# Seeed_Studio_XIAO_nRF52840_v1_1.net
KiCad netlist of a schematic drawn in EAGLE
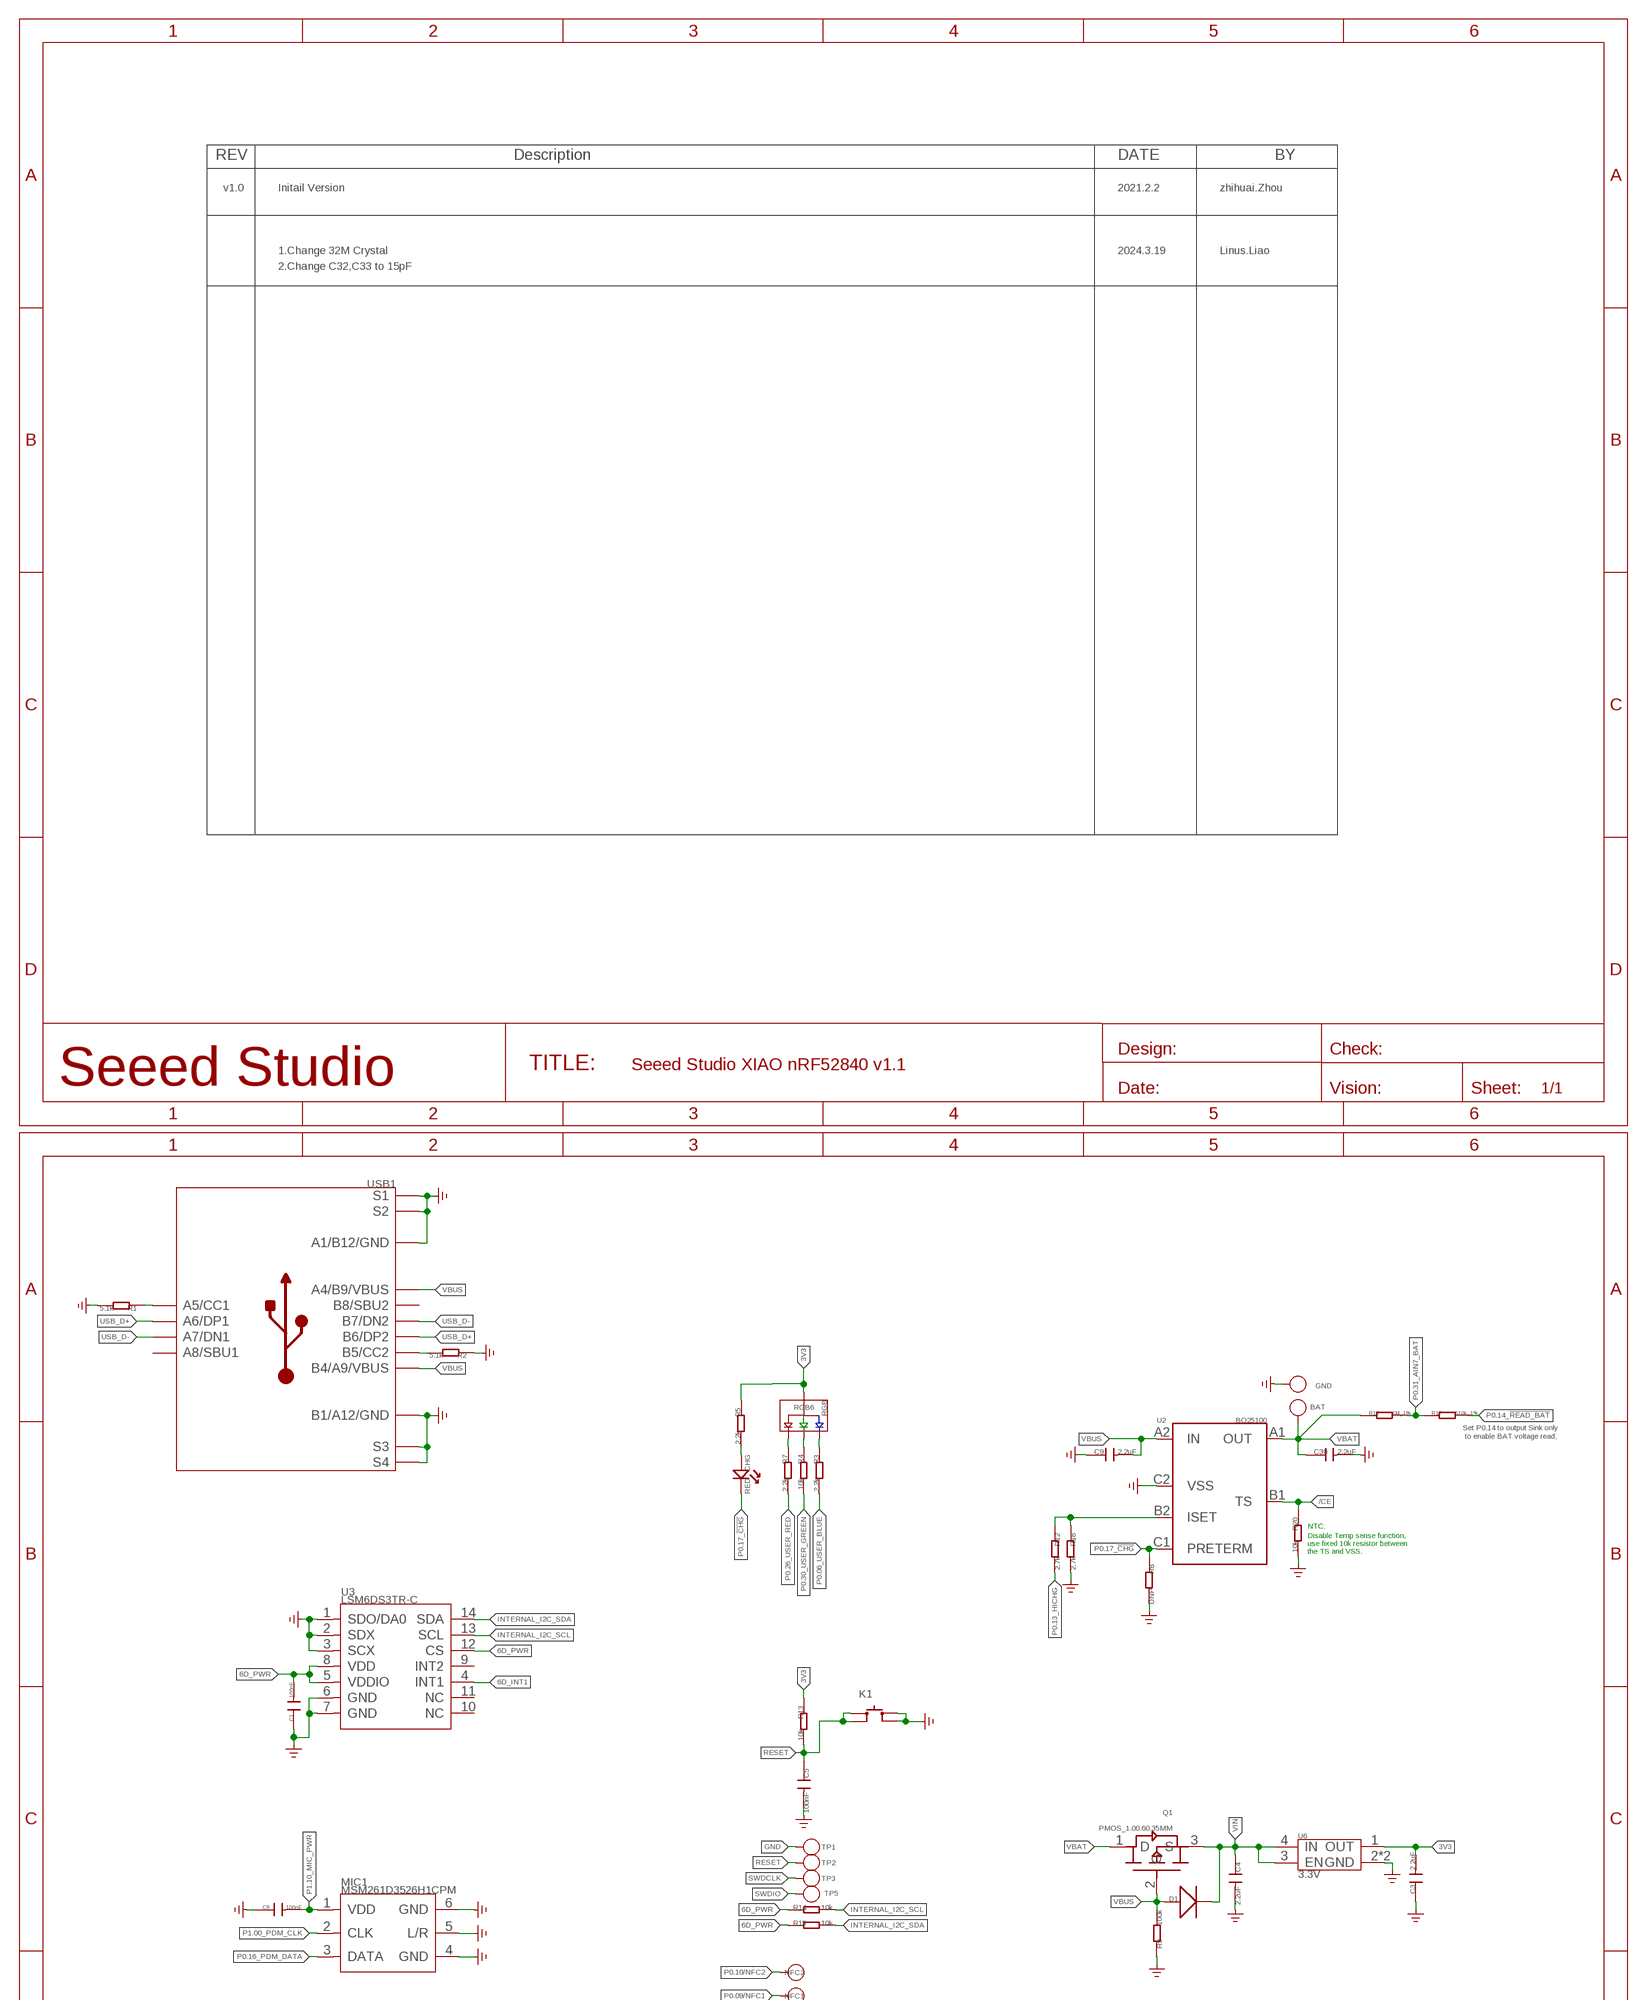
[diagram p0: schematic, sheet 1, part 1 of 2]
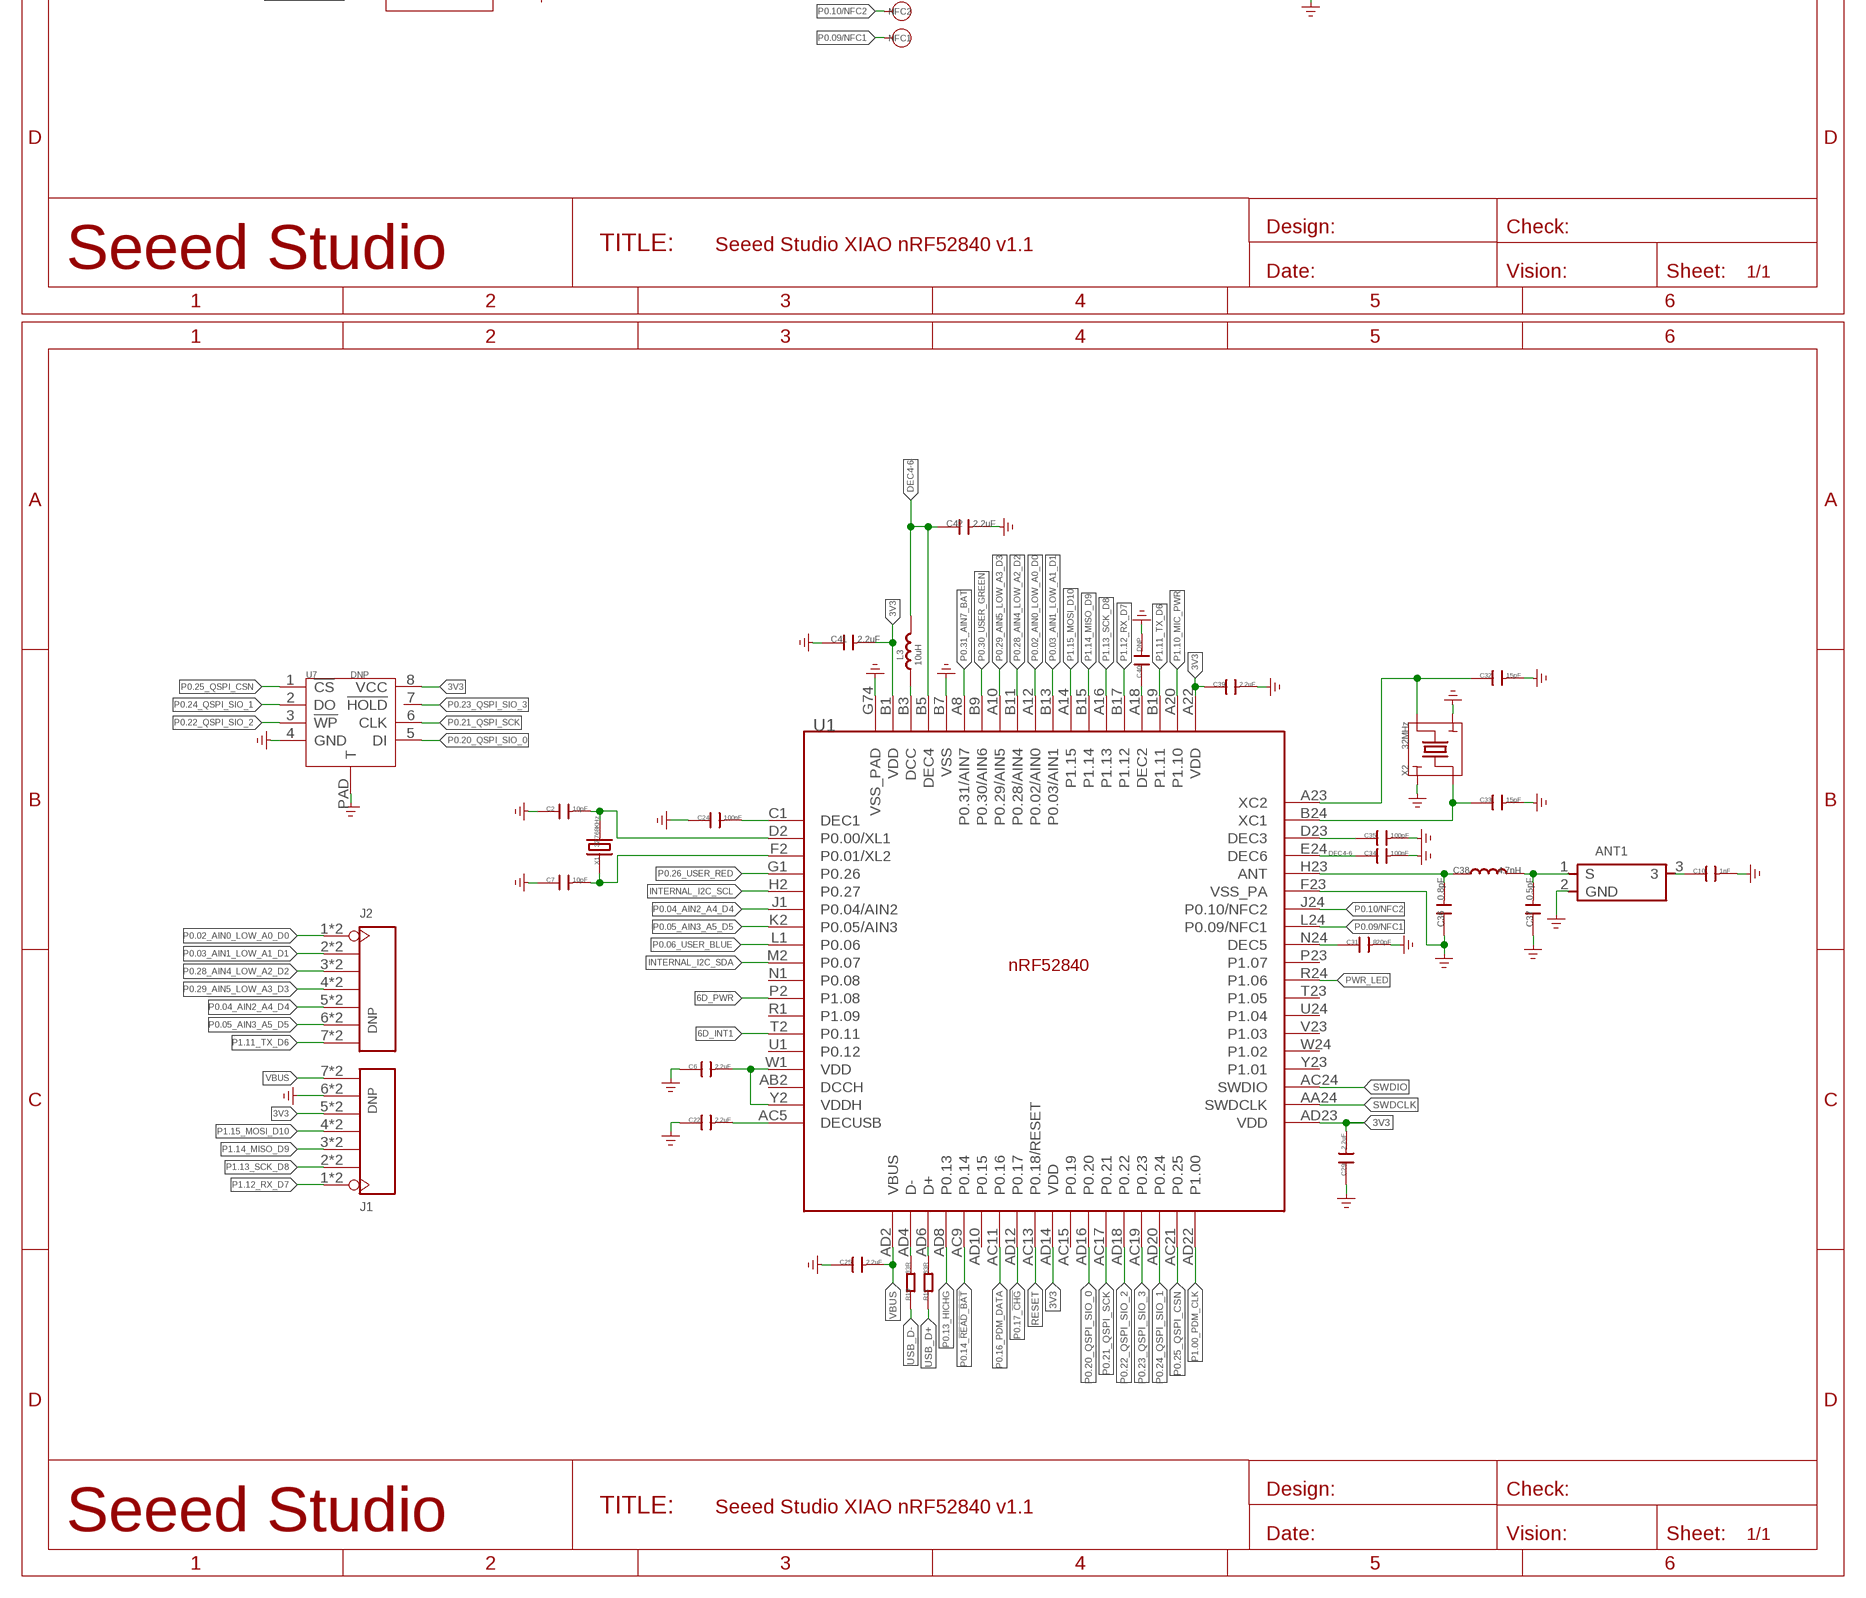
[diagram p1: schematic, sheet 1, part 2 of 2]

(export (version "E")
  (design (tool "Eeschema 10.0.6"))
  (components
    (comp (ref "ANT1")
      (value "ANTENNA-AN3216")
      (footprint "eagle-import:ANT-SMD3P-3.2X1.6X1.04MM")
      (libsource (lib "eagle-import") (part "ANTENNA-AN3216"))
    )
    (comp (ref "BAT")
      (value "TEST-POINT'4080'")
      (footprint "eagle-import:TP-80X40MIL")
      (libsource (lib "eagle-import") (part "TEST-POINT'4080'"))
    )
    (comp (ref "C1")
      (value "100nF")
      (footprint "eagle-import:C0201")
      (libsource (lib "eagle-import") (part "C-0201"))
    )
    (comp (ref "C2")
      (value "10pF")
      (footprint "eagle-import:C0201")
      (libsource (lib "eagle-import") (part "C-0201"))
    )
    (comp (ref "C3")
      (value "2.2uF")
      (footprint "eagle-import:C0201")
      (libsource (lib "eagle-import") (part "C-0201"))
    )
    (comp (ref "C4")
      (value "2.2uF")
      (footprint "eagle-import:C0201")
      (libsource (lib "eagle-import") (part "C-0201"))
    )
    (comp (ref "C5")
      (value "100nF")
      (footprint "eagle-import:C0201")
      (libsource (lib "eagle-import") (part "C-0201"))
    )
    (comp (ref "C6")
      (value "2.2uF")
      (footprint "eagle-import:C0201")
      (libsource (lib "eagle-import") (part "C-0201"))
    )
    (comp (ref "C7")
      (value "10pF")
      (footprint "eagle-import:C0201")
      (libsource (lib "eagle-import") (part "C-0201"))
    )
    (comp (ref "C8")
      (value "100nF")
      (footprint "eagle-import:C0201")
      (libsource (lib "eagle-import") (part "C-0201"))
    )
    (comp (ref "C9")
      (value "2.2uF")
      (footprint "eagle-import:C0201")
      (libsource (lib "eagle-import") (part "C-0201"))
    )
    (comp (ref "C10")
      (value "1nF")
      (footprint "eagle-import:C0402")
      (libsource (lib "eagle-import") (part "C-0402"))
    )
    (comp (ref "C22")
      (value "2.2uF")
      (footprint "eagle-import:C0201")
      (libsource (lib "eagle-import") (part "C-0201"))
    )
    (comp (ref "C24")
      (value "100nF")
      (footprint "eagle-import:C0201")
      (libsource (lib "eagle-import") (part "C-0201"))
    )
    (comp (ref "C25")
      (value "2.2uF")
      (footprint "eagle-import:C0201")
      (libsource (lib "eagle-import") (part "C-0201"))
    )
    (comp (ref "C29")
      (value "2.2uF")
      (footprint "eagle-import:C0201")
      (libsource (lib "eagle-import") (part "C-0201"))
    )
    (comp (ref "C30")
      (value "2.2uF")
      (footprint "eagle-import:C0201")
      (libsource (lib "eagle-import") (part "C-0201"))
    )
    (comp (ref "C31")
      (value "820pF")
      (footprint "eagle-import:C0201")
      (libsource (lib "eagle-import") (part "C-0201"))
    )
    (comp (ref "C32")
      (value "15pF")
      (footprint "eagle-import:C0201")
      (libsource (lib "eagle-import") (part "C-0201"))
    )
    (comp (ref "C33")
      (value "15pF")
      (footprint "eagle-import:C0201")
      (libsource (lib "eagle-import") (part "C-0201"))
    )
    (comp (ref "C34")
      (value "100nF")
      (footprint "eagle-import:C0201")
      (libsource (lib "eagle-import") (part "C-0201"))
    )
    (comp (ref "C35")
      (value "100pF")
      (footprint "eagle-import:C0201")
      (libsource (lib "eagle-import") (part "C-0201"))
    )
    (comp (ref "C36")
      (value "0.8pF")
      (footprint "eagle-import:C0201")
      (libsource (lib "eagle-import") (part "C-0201"))
    )
    (comp (ref "C37")
      (value "0.5pF")
      (footprint "eagle-import:C0201")
      (libsource (lib "eagle-import") (part "C-0201"))
    )
    (comp (ref "C38")
      (value "4.7nH")
      (footprint "eagle-import:L0201")
      (libsource (lib "eagle-import") (part "L0201"))
    )
    (comp (ref "C39")
      (value "2.2uF")
      (footprint "eagle-import:C0201")
      (libsource (lib "eagle-import") (part "C-0201"))
    )
    (comp (ref "C40")
      (value "DNP")
      (footprint "eagle-import:C0201")
      (libsource (lib "eagle-import") (part "C-0201"))
    )
    (comp (ref "C41")
      (value "2.2uF")
      (footprint "eagle-import:C0201")
      (libsource (lib "eagle-import") (part "C-0201"))
    )
    (comp (ref "C42")
      (value "2.2uF")
      (footprint "eagle-import:C0201")
      (libsource (lib "eagle-import") (part "C-0201"))
    )
    (comp (ref "CHG")
      (value "RED")
      (footprint "eagle-import:LED-0402")
      (libsource (lib "eagle-import") (part "LED-0402"))
    )
    (comp (ref "D1")
      (value "DIODE'0603'")
      (footprint "eagle-import:SOD-523")
      (libsource (lib "eagle-import") (part "DIODE'0603'"))
    )
    (comp (ref "GND")
      (value "GND")
      (footprint "eagle-import:TP-80X40MIL")
      (libsource (lib "eagle-import") (part "TEST-POINT'4080'"))
    )
    (comp (ref "J1")
      (value "DNP")
      (footprint "eagle-import:H7-HALF-HOLE-2.54")
      (libsource (lib "eagle-import") (part "HEADER-7P-HALF-HOLE-2.54"))
    )
    (comp (ref "J2")
      (value "DNP")
      (footprint "eagle-import:H7-HALF-HOLE-2.54")
      (libsource (lib "eagle-import") (part "HEADER-7P-HALF-HOLE-2.54"))
    )
    (comp (ref "K1")
      (value "BUTTON-4P")
      (footprint "eagle-import:SW4-SMD-2.8-2.6X1.6X0.53MM")
      (libsource (lib "eagle-import") (part "BUTTON-4P"))
    )
    (comp (ref "L3")
      (value "10uH")
      (footprint "eagle-import:L0603")
      (libsource (lib "eagle-import") (part "L0603"))
    )
    (comp (ref "MIC1")
      (value "MSM261D3526H1CPM")
      (footprint "eagle-import:MIC6P-3.5X2.65X0.94MM")
      (libsource (lib "eagle-import") (part "MIC-MSM261D3526H1CPM"))
    )
    (comp (ref "NFC1")
      (value "TEST-POINT'4080'")
      (footprint "eagle-import:TP-80X40MIL")
      (libsource (lib "eagle-import") (part "TEST-POINT'4080'"))
    )
    (comp (ref "NFC2")
      (value "TEST-POINT'4080'")
      (footprint "eagle-import:TP-80X40MIL")
      (libsource (lib "eagle-import") (part "TEST-POINT'4080'"))
    )
    (comp (ref "Q1")
      (value "PMOS_1.00.60.35MM")
      (footprint "eagle-import:PMOS_1.0_0.6_0.35MM")
      (libsource (lib "eagle-import") (part "PMOS_1.00.60.35MM"))
    )
    (comp (ref "R1")
      (value "5.1k")
      (footprint "eagle-import:R0201")
      (libsource (lib "eagle-import") (part "R-0201"))
    )
    (comp (ref "R2")
      (value "5.1k")
      (footprint "eagle-import:R0201")
      (libsource (lib "eagle-import") (part "R-0201"))
    )
    (comp (ref "R3")
      (value "2.2k")
      (footprint "eagle-import:R0201")
      (libsource (lib "eagle-import") (part "R-0201"))
    )
    (comp (ref "R4")
      (value "10k")
      (footprint "eagle-import:R0201")
      (libsource (lib "eagle-import") (part "R-0201"))
    )
    (comp (ref "R5")
      (value "2.2k")
      (footprint "eagle-import:R0201")
      (libsource (lib "eagle-import") (part "R-0201"))
    )
    (comp (ref "R7")
      (value "2.2k")
      (footprint "eagle-import:R0201")
      (libsource (lib "eagle-import") (part "R-0201"))
    )
    (comp (ref "R8")
      (value "DNP")
      (footprint "eagle-import:R0201")
      (libsource (lib "eagle-import") (part "R-0201"))
    )
    (comp (ref "R9")
      (value "100k")
      (footprint "eagle-import:R0201")
      (libsource (lib "eagle-import") (part "R-0201"))
    )
    (comp (ref "R10")
      (value "33R")
      (footprint "eagle-import:R0201")
      (libsource (lib "eagle-import") (part "R-0201"))
    )
    (comp (ref "R11")
      (value "33R")
      (footprint "eagle-import:R0201")
      (libsource (lib "eagle-import") (part "R-0201"))
    )
    (comp (ref "R12")
      (value "2.7k")
      (footprint "eagle-import:R0201")
      (libsource (lib "eagle-import") (part "R-0201"))
    )
    (comp (ref "R13")
      (value "10k")
      (footprint "eagle-import:R0201")
      (libsource (lib "eagle-import") (part "R-0201"))
    )
    (comp (ref "R14")
      (value "10k")
      (footprint "eagle-import:R0201")
      (libsource (lib "eagle-import") (part "R-0201"))
    )
    (comp (ref "R15")
      (value "10k")
      (footprint "eagle-import:R0201")
      (libsource (lib "eagle-import") (part "R-0201"))
    )
    (comp (ref "R16")
      (value "1M_1%")
      (footprint "eagle-import:R0201")
      (libsource (lib "eagle-import") (part "R-0201"))
    )
    (comp (ref "R17")
      (value "510k_1%")
      (footprint "eagle-import:R0201")
      (libsource (lib "eagle-import") (part "R-0201"))
    )
    (comp (ref "R18")
      (value "2.7k")
      (footprint "eagle-import:R0201")
      (libsource (lib "eagle-import") (part "R-0201"))
    )
    (comp (ref "R20")
      (value "10k")
      (footprint "eagle-import:R0201")
      (libsource (lib "eagle-import") (part "R-0201"))
    )
    (comp (ref "RGB6")
      (value "RGB")
      (footprint "eagle-import:4P1010")
      (libsource (lib "eagle-import") (part "RGB-1010"))
    )
    (comp (ref "TP1")
      (value "TEST-POINT'4545'")
      (footprint "eagle-import:TP-D45MIL")
      (fields (field (name "PARTNO") "DNP"))
      (libsource (lib "eagle-import") (part "TEST-POINT'4545'"))
    )
    (comp (ref "TP2")
      (value "TEST-POINT'4545'")
      (footprint "eagle-import:TP-D45MIL")
      (fields (field (name "PARTNO") "DNP"))
      (libsource (lib "eagle-import") (part "TEST-POINT'4545'"))
    )
    (comp (ref "TP3")
      (value "TEST-POINT'4545'")
      (footprint "eagle-import:TP-D45MIL")
      (fields (field (name "PARTNO") "DNP"))
      (libsource (lib "eagle-import") (part "TEST-POINT'4545'"))
    )
    (comp (ref "TP5")
      (value "TEST-POINT'4545'")
      (footprint "eagle-import:TP-D45MIL")
      (fields (field (name "PARTNO") "DNP"))
      (libsource (lib "eagle-import") (part "TEST-POINT'4545'"))
    )
    (comp (ref "U1")
      (value "NRF52840_QF")
      (footprint "eagle-import:AQFN50P700X700X85_HS-74N")
      (libsource (lib "eagle-import") (part "NRF52840_QF"))
    )
    (comp (ref "U2")
      (value "BQ25100")
      (footprint "eagle-import:BQ25101_DSBGA_6_BQ25101")
      (libsource (lib "eagle-import") (part "BQ25101_DSBGA_6_BQ25101_DSBGA_6"))
    )
    (comp (ref "U3")
      (value "LSM6DS3TR-C")
      (footprint "eagle-import:LGA14-0.5-2.5X3X0.86MM")
      (libsource (lib "eagle-import") (part "SENSOR-LSM6DS3TR-C"))
    )
    (comp (ref "U6")
      (value "3.3V")
      (footprint "eagle-import:X2SON-4")
      (libsource (lib "eagle-import") (part "TLV733P"))
    )
    (comp (ref "U7")
      (value "DNP")
      (footprint "eagle-import:USON2X3_8")
      (libsource (lib "eagle-import") (part "W25XXC"))
    )
    (comp (ref "USB1")
      (value "USB2.0-TYPE-C")
      (footprint "eagle-import:USB2.0-TYPE-C")
      (libsource (lib "eagle-import") (part "USB2.0-TYPE-C"))
    )
    (comp (ref "X1")
      (value "32.768KHz")
      (footprint "eagle-import:X2-SMD-L1.6X1.0X0.5MM")
      (libsource (lib "eagle-import") (part "CRYSTAL-2P-1610"))
    )
    (comp (ref "X2")
      (value "32MHz")
      (footprint "eagle-import:4P1612")
      (libsource (lib "eagle-import") (part "CRYSTAL'-1612'"))
    )
  )
  (nets
    (net (code "1") (name "/P0.14_~{READ_BAT}") (class "Default")
      (node (ref "R17") (pin "2") (pinfunction "2_2") (pintype "passive"))
      (node (ref "U1") (pin "AC9") (pinfunction "P0.14_AC9") (pintype "bidirectional"))
    )
    (net (code "2") (name "/P0.17_~{CHG}") (class "Default")
      (node (ref "CHG") (pin "-") (pinfunction "-_-") (pintype "passive"))
      (node (ref "R8") (pin "1") (pinfunction "1_1") (pintype "passive"))
      (node (ref "U1") (pin "AD12") (pinfunction "P0.17_AD12") (pintype "bidirectional"))
      (node (ref "U2") (pin "C1") (pinfunction "PRETERM_C1") (pintype "bidirectional"))
    )
    (net (code "3") (name "3V3") (class "Default")
      (node (ref "C29") (pin "2") (pinfunction "2_2") (pintype "passive"))
      (node (ref "C3") (pin "2") (pinfunction "2_2") (pintype "passive"))
      (node (ref "C39") (pin "1") (pinfunction "1_1") (pintype "passive"))
      (node (ref "C41") (pin "2") (pinfunction "2_2") (pintype "passive"))
      (node (ref "C6") (pin "2") (pinfunction "2_2") (pintype "passive"))
      (node (ref "J1") (pin "17") (pinfunction "5_17") (pintype "bidirectional"))
      (node (ref "J1") (pin "5") (pinfunction "5_5") (pintype "bidirectional"))
      (node (ref "R13") (pin "1") (pinfunction "1_1") (pintype "passive"))
      (node (ref "R5") (pin "1") (pinfunction "1_1") (pintype "passive"))
      (node (ref "RGB6") (pin "+") (pinfunction "+_+") (pintype "bidirectional"))
      (node (ref "U1") (pin "A22") (pinfunction "VDD_A22") (pintype "bidirectional"))
      (node (ref "U1") (pin "AD14") (pinfunction "VDD_AD14") (pintype "bidirectional"))
      (node (ref "U1") (pin "AD23") (pinfunction "VDD_AD23") (pintype "bidirectional"))
      (node (ref "U1") (pin "B1") (pinfunction "VDD_B1") (pintype "bidirectional"))
      (node (ref "U1") (pin "W1") (pinfunction "VDD_W1") (pintype "bidirectional"))
      (node (ref "U1") (pin "Y2") (pinfunction "VDDH_Y2") (pintype "bidirectional"))
      (node (ref "U6") (pin "1") (pinfunction "OUT_1") (pintype "bidirectional"))
      (node (ref "U7") (pin "8") (pinfunction "VCC_8") (pintype "bidirectional"))
    )
    (net (code "4") (name "6D_INT1") (class "Default")
      (node (ref "U1") (pin "T2") (pinfunction "P0.11_T2") (pintype "bidirectional"))
      (node (ref "U3") (pin "4") (pinfunction "INT1_4") (pintype "bidirectional"))
    )
    (net (code "5") (name "6D_PWR") (class "Default")
      (node (ref "C1") (pin "2") (pinfunction "2_2") (pintype "passive"))
      (node (ref "R14") (pin "1") (pinfunction "1_1") (pintype "passive"))
      (node (ref "R15") (pin "1") (pinfunction "1_1") (pintype "passive"))
      (node (ref "U1") (pin "P2") (pinfunction "P1.08_P2") (pintype "bidirectional"))
      (node (ref "U3") (pin "12") (pinfunction "CS_12") (pintype "bidirectional"))
      (node (ref "U3") (pin "5") (pinfunction "VDDIO_5") (pintype "bidirectional"))
      (node (ref "U3") (pin "8") (pinfunction "VDD_8") (pintype "bidirectional"))
    )
    (net (code "6") (name "DEC4-6") (class "Default")
      (node (ref "C34") (pin "1") (pinfunction "1_1") (pintype "passive"))
      (node (ref "C42") (pin "1") (pinfunction "1_1") (pintype "passive"))
      (node (ref "L3") (pin "2") (pinfunction "2_2") (pintype "passive"))
      (node (ref "U1") (pin "B5") (pinfunction "DEC4_B5") (pintype "bidirectional"))
      (node (ref "U1") (pin "E24") (pinfunction "DEC6_E24") (pintype "bidirectional"))
    )
    (net (code "7") (name "GND") (class "Default")
      (node (ref "ANT1") (pin "2") (pinfunction "GND_2") (pintype "bidirectional"))
      (node (ref "C1") (pin "1") (pinfunction "1_1") (pintype "passive"))
      (node (ref "C10") (pin "2") (pinfunction "2_2") (pintype "passive"))
      (node (ref "C2") (pin "1") (pinfunction "1_1") (pintype "passive"))
      (node (ref "C22") (pin "1") (pinfunction "1_1") (pintype "passive"))
      (node (ref "C24") (pin "1") (pinfunction "1_1") (pintype "passive"))
      (node (ref "C25") (pin "1") (pinfunction "1_1") (pintype "passive"))
      (node (ref "C29") (pin "1") (pinfunction "1_1") (pintype "passive"))
      (node (ref "C3") (pin "1") (pinfunction "1_1") (pintype "passive"))
      (node (ref "C30") (pin "2") (pinfunction "2_2") (pintype "passive"))
      (node (ref "C31") (pin "2") (pinfunction "2_2") (pintype "passive"))
      (node (ref "C32") (pin "2") (pinfunction "2_2") (pintype "passive"))
      (node (ref "C33") (pin "2") (pinfunction "2_2") (pintype "passive"))
      (node (ref "C34") (pin "2") (pinfunction "2_2") (pintype "passive"))
      (node (ref "C35") (pin "2") (pinfunction "2_2") (pintype "passive"))
      (node (ref "C36") (pin "1") (pinfunction "1_1") (pintype "passive"))
      (node (ref "C37") (pin "1") (pinfunction "1_1") (pintype "passive"))
      (node (ref "C39") (pin "2") (pinfunction "2_2") (pintype "passive"))
      (node (ref "C4") (pin "2") (pinfunction "2_2") (pintype "passive"))
      (node (ref "C40") (pin "2") (pinfunction "2_2") (pintype "passive"))
      (node (ref "C41") (pin "1") (pinfunction "1_1") (pintype "passive"))
      (node (ref "C42") (pin "2") (pinfunction "2_2") (pintype "passive"))
      (node (ref "C5") (pin "2") (pinfunction "2_2") (pintype "passive"))
      (node (ref "C6") (pin "1") (pinfunction "1_1") (pintype "passive"))
      (node (ref "C7") (pin "1") (pinfunction "1_1") (pintype "passive"))
      (node (ref "C8") (pin "1") (pinfunction "1_1") (pintype "passive"))
      (node (ref "C9") (pin "1") (pinfunction "1_1") (pintype "passive"))
      (node (ref "GND") (pin "1") (pinfunction "T_1") (pintype "bidirectional"))
      (node (ref "J1") (pin "18") (pinfunction "6_18") (pintype "bidirectional"))
      (node (ref "J1") (pin "6") (pinfunction "6_6") (pintype "bidirectional"))
      (node (ref "K1") (pin "2") (pinfunction "B0_2") (pintype "bidirectional"))
      (node (ref "K1") (pin "4") (pinfunction "B1_4") (pintype "bidirectional"))
      (node (ref "MIC1") (pin "4") (pinfunction "GND_4") (pintype "bidirectional"))
      (node (ref "MIC1") (pin "5") (pinfunction "L/R_5") (pintype "bidirectional"))
      (node (ref "MIC1") (pin "6") (pinfunction "GND_6") (pintype "bidirectional"))
      (node (ref "R1") (pin "2") (pinfunction "2_2") (pintype "passive"))
      (node (ref "R18") (pin "2") (pinfunction "2_2") (pintype "passive"))
      (node (ref "R2") (pin "1") (pinfunction "1_1") (pintype "passive"))
      (node (ref "R20") (pin "2") (pinfunction "2_2") (pintype "passive"))
      (node (ref "R8") (pin "2") (pinfunction "2_2") (pintype "passive"))
      (node (ref "R9") (pin "1") (pinfunction "1_1") (pintype "passive"))
      (node (ref "TP1") (pin "T") (pinfunction "T_T") (pintype "bidirectional"))
      (node (ref "U1") (pin "B7") (pinfunction "VSS_B7") (pintype "bidirectional"))
      (node (ref "U1") (pin "F23") (pinfunction "VSS_PA_F23") (pintype "bidirectional"))
      (node (ref "U1") (pin "G74") (pinfunction "VSS_PAD_G74") (pintype "bidirectional"))
      (node (ref "U2") (pin "C2") (pinfunction "VSS_C2") (pintype "bidirectional"))
      (node (ref "U3") (pin "1") (pinfunction "SDO/DA0_1") (pintype "bidirectional"))
      (node (ref "U3") (pin "2") (pinfunction "SDX_2") (pintype "bidirectional"))
      (node (ref "U3") (pin "3") (pinfunction "SCX_3") (pintype "bidirectional"))
      (node (ref "U3") (pin "6") (pinfunction "GND_6") (pintype "bidirectional"))
      (node (ref "U3") (pin "7") (pinfunction "GND_7") (pintype "bidirectional"))
      (node (ref "U6") (pin "2") (pinfunction "GND_2") (pintype "bidirectional"))
      (node (ref "U6") (pin "T") (pinfunction "GND_T") (pintype "bidirectional"))
      (node (ref "U7") (pin "4") (pinfunction "GND_4") (pintype "bidirectional"))
      (node (ref "U7") (pin "PAD") (pinfunction "T_PAD") (pintype "bidirectional"))
      (node (ref "USB1") (pin "A1_B12") (pinfunction "A1/B12/GND_A1_B12") (pintype "bidirectional"))
      (node (ref "USB1") (pin "B1_A12") (pinfunction "B1/A12/GND_B1_A12") (pintype "bidirectional"))
      (node (ref "USB1") (pin "S1") (pinfunction "S1_S1") (pintype "bidirectional"))
      (node (ref "USB1") (pin "S2") (pinfunction "S2_S2") (pintype "bidirectional"))
      (node (ref "USB1") (pin "S3") (pinfunction "S3_S3") (pintype "bidirectional"))
      (node (ref "USB1") (pin "S4") (pinfunction "S4_S4") (pintype "bidirectional"))
      (node (ref "USB1") (pin "S5") (pinfunction "S1_S5") (pintype "bidirectional"))
      (node (ref "USB1") (pin "S6") (pinfunction "S2_S6") (pintype "bidirectional"))
      (node (ref "X2") (pin "2") (pinfunction "1_2") (pintype "bidirectional"))
      (node (ref "X2") (pin "4") (pinfunction "3_4") (pintype "bidirectional"))
    )
    (net (code "8") (name "INTERNAL_I2C_SCL") (class "Default")
      (node (ref "R14") (pin "2") (pinfunction "2_2") (pintype "passive"))
      (node (ref "U1") (pin "H2") (pinfunction "P0.27_H2") (pintype "bidirectional"))
      (node (ref "U3") (pin "13") (pinfunction "SCL_13") (pintype "bidirectional"))
    )
    (net (code "9") (name "INTERNAL_I2C_SDA") (class "Default")
      (node (ref "R15") (pin "2") (pinfunction "2_2") (pintype "passive"))
      (node (ref "U1") (pin "M2") (pinfunction "P0.07_M2") (pintype "bidirectional"))
      (node (ref "U3") (pin "14") (pinfunction "SDA_14") (pintype "bidirectional"))
    )
    (net (code "10") (name "Net-(ANT1-Pad3)") (class "Default")
      (node (ref "ANT1") (pin "3") (pinfunction "3_3") (pintype "bidirectional"))
      (node (ref "C10") (pin "1") (pinfunction "1_1") (pintype "passive"))
    )
    (net (code "11") (name "Net-(ANT1-S)") (class "Default")
      (node (ref "ANT1") (pin "1") (pinfunction "S_1") (pintype "bidirectional"))
      (node (ref "C37") (pin "2") (pinfunction "2_2") (pintype "passive"))
      (node (ref "C38") (pin "2") (pinfunction "2_2") (pintype "passive"))
    )
    (net (code "12") (name "Net-(CHG-Pad+)") (class "Default")
      (node (ref "CHG") (pin "+") (pinfunction "+_+") (pintype "passive"))
      (node (ref "R5") (pin "2") (pinfunction "2_2") (pintype "passive"))
    )
    (net (code "13") (name "Net-(R3-Pad1)") (class "Default")
      (node (ref "R3") (pin "1") (pinfunction "1_1") (pintype "passive"))
      (node (ref "RGB6") (pin "B-") (pinfunction "B-_B-") (pintype "bidirectional"))
    )
    (net (code "14") (name "Net-(R4-Pad1)") (class "Default")
      (node (ref "R4") (pin "1") (pinfunction "1_1") (pintype "passive"))
      (node (ref "RGB6") (pin "G-") (pinfunction "G-_G-") (pintype "bidirectional"))
    )
    (net (code "15") (name "Net-(R7-Pad1)") (class "Default")
      (node (ref "R7") (pin "1") (pinfunction "1_1") (pintype "passive"))
      (node (ref "RGB6") (pin "R-") (pinfunction "R-_R-") (pintype "bidirectional"))
    )
    (net (code "16") (name "Net-(U1-ANT)") (class "Default")
      (node (ref "C36") (pin "2") (pinfunction "2_2") (pintype "passive"))
      (node (ref "C38") (pin "1") (pinfunction "1_1") (pintype "passive"))
      (node (ref "U1") (pin "H23") (pinfunction "ANT_H23") (pintype "bidirectional"))
    )
    (net (code "17") (name "Net-(U1-D+)") (class "Default")
      (node (ref "R11") (pin "2") (pinfunction "2_2") (pintype "passive"))
      (node (ref "U1") (pin "AD6") (pinfunction "D+_AD6") (pintype "bidirectional"))
    )
    (net (code "18") (name "Net-(U1-D-)") (class "Default")
      (node (ref "R10") (pin "2") (pinfunction "2_2") (pintype "passive"))
      (node (ref "U1") (pin "AD4") (pinfunction "D-_AD4") (pintype "bidirectional"))
    )
    (net (code "19") (name "Net-(U1-DCC)") (class "Default")
      (node (ref "L3") (pin "1") (pinfunction "1_1") (pintype "passive"))
      (node (ref "U1") (pin "B3") (pinfunction "DCC_B3") (pintype "bidirectional"))
    )
    (net (code "20") (name "Net-(U1-DEC1)") (class "Default")
      (node (ref "C24") (pin "2") (pinfunction "2_2") (pintype "passive"))
      (node (ref "U1") (pin "C1") (pinfunction "DEC1_C1") (pintype "bidirectional"))
    )
    (net (code "21") (name "Net-(U1-DEC2)") (class "Default")
      (node (ref "C40") (pin "1") (pinfunction "1_1") (pintype "passive"))
      (node (ref "U1") (pin "A18") (pinfunction "DEC2_A18") (pintype "bidirectional"))
    )
    (net (code "22") (name "Net-(U1-DEC3)") (class "Default")
      (node (ref "C35") (pin "1") (pinfunction "1_1") (pintype "passive"))
      (node (ref "U1") (pin "D23") (pinfunction "DEC3_D23") (pintype "bidirectional"))
    )
    (net (code "23") (name "Net-(U1-DEC5)") (class "Default")
      (node (ref "C31") (pin "1") (pinfunction "1_1") (pintype "passive"))
      (node (ref "U1") (pin "N24") (pinfunction "DEC5_N24") (pintype "bidirectional"))
    )
    (net (code "24") (name "Net-(U1-DECUSB)") (class "Default")
      (node (ref "C22") (pin "2") (pinfunction "2_2") (pintype "passive"))
      (node (ref "U1") (pin "AC5") (pinfunction "DECUSB_AC5") (pintype "bidirectional"))
    )
    (net (code "25") (name "Net-(U1-P0.00{slash}XL1)") (class "Default")
      (node (ref "C2") (pin "2") (pinfunction "2_2") (pintype "passive"))
      (node (ref "U1") (pin "D2") (pinfunction "P0.00/XL1_D2") (pintype "bidirectional"))
      (node (ref "X1") (pin "2") (pinfunction "2_2") (pintype "passive"))
    )
    (net (code "26") (name "Net-(U1-P0.01{slash}XL2)") (class "Default")
      (node (ref "C7") (pin "2") (pinfunction "2_2") (pintype "passive"))
      (node (ref "U1") (pin "F2") (pinfunction "P0.01/XL2_F2") (pintype "bidirectional"))
      (node (ref "X1") (pin "1") (pinfunction "1_1") (pintype "passive"))
    )
    (net (code "27") (name "Net-(U1-XC1)") (class "Default")
      (node (ref "C33") (pin "1") (pinfunction "1_1") (pintype "passive"))
      (node (ref "U1") (pin "B24") (pinfunction "XC1_B24") (pintype "bidirectional"))
      (node (ref "X2") (pin "1") (pinfunction "2_1") (pintype "passive"))
    )
    (net (code "28") (name "Net-(U1-XC2)") (class "Default")
      (node (ref "C32") (pin "1") (pinfunction "1_1") (pintype "passive"))
      (node (ref "U1") (pin "A23") (pinfunction "XC2_A23") (pintype "bidirectional"))
      (node (ref "X2") (pin "3") (pinfunction "4_3") (pintype "passive"))
    )
    (net (code "29") (name "Net-(U2-ISET)") (class "Default")
      (node (ref "R12") (pin "1") (pinfunction "1_1") (pintype "passive"))
      (node (ref "R18") (pin "1") (pinfunction "1_1") (pintype "passive"))
      (node (ref "U2") (pin "B2") (pinfunction "ISET_B2") (pintype "bidirectional"))
    )
    (net (code "30") (name "Net-(USB1-A5{slash}CC1)") (class "Default")
      (node (ref "R1") (pin "1") (pinfunction "1_1") (pintype "passive"))
      (node (ref "USB1") (pin "A5") (pinfunction "A5/CC1_A5") (pintype "bidirectional"))
    )
    (net (code "31") (name "Net-(USB1-B5{slash}CC2)") (class "Default")
      (node (ref "R2") (pin "2") (pinfunction "2_2") (pintype "passive"))
      (node (ref "USB1") (pin "B5") (pinfunction "B5/CC2_B5") (pintype "bidirectional"))
    )
    (net (code "32") (name "P0.02_AIN0_LOW_A0_D0") (class "Default")
      (node (ref "J2") (pin "1") (pinfunction "1_1") (pintype "bidirectional"))
      (node (ref "J2") (pin "13") (pinfunction "1_13") (pintype "bidirectional"))
      (node (ref "U1") (pin "A12") (pinfunction "P0.02/AIN0_A12") (pintype "bidirectional"))
    )
    (net (code "33") (name "P0.03_AIN1_LOW_A1_D1") (class "Default")
      (node (ref "J2") (pin "14") (pinfunction "2_14") (pintype "bidirectional"))
      (node (ref "J2") (pin "2") (pinfunction "2_2") (pintype "bidirectional"))
      (node (ref "U1") (pin "B13") (pinfunction "P0.03/AIN1_B13") (pintype "bidirectional"))
    )
    (net (code "34") (name "P0.04_AIN2_A4_D4") (class "Default")
      (node (ref "J2") (pin "17") (pinfunction "5_17") (pintype "bidirectional"))
      (node (ref "J2") (pin "5") (pinfunction "5_5") (pintype "bidirectional"))
      (node (ref "U1") (pin "J1") (pinfunction "P0.04/AIN2_J1") (pintype "bidirectional"))
    )
    (net (code "35") (name "P0.05_AIN3_A5_D5") (class "Default")
      (node (ref "J2") (pin "18") (pinfunction "6_18") (pintype "bidirectional"))
      (node (ref "J2") (pin "6") (pinfunction "6_6") (pintype "bidirectional"))
      (node (ref "U1") (pin "K2") (pinfunction "P0.05/AIN3_K2") (pintype "bidirectional"))
    )
    (net (code "36") (name "P0.06_USER_BLUE") (class "Default")
      (node (ref "R3") (pin "2") (pinfunction "2_2") (pintype "passive"))
      (node (ref "U1") (pin "L1") (pinfunction "P0.06_L1") (pintype "bidirectional"))
    )
    (net (code "37") (name "P0.09{slash}NFC1") (class "Default")
      (node (ref "NFC1") (pin "1") (pinfunction "T_1") (pintype "bidirectional"))
      (node (ref "U1") (pin "L24") (pinfunction "P0.09/NFC1_L24") (pintype "bidirectional"))
    )
    (net (code "38") (name "P0.10{slash}NFC2") (class "Default")
      (node (ref "NFC2") (pin "1") (pinfunction "T_1") (pintype "bidirectional"))
      (node (ref "U1") (pin "J24") (pinfunction "P0.10/NFC2_J24") (pintype "bidirectional"))
    )
    (net (code "39") (name "P0.13_HICHG") (class "Default")
      (node (ref "R12") (pin "2") (pinfunction "2_2") (pintype "passive"))
      (node (ref "U1") (pin "AD8") (pinfunction "P0.13_AD8") (pintype "bidirectional"))
    )
    (net (code "40") (name "P0.16_PDM_DATA") (class "Default")
      (node (ref "MIC1") (pin "3") (pinfunction "DATA_3") (pintype "bidirectional"))
      (node (ref "U1") (pin "AC11") (pinfunction "P0.16_AC11") (pintype "bidirectional"))
    )
    (net (code "41") (name "P0.20_QSPI_SIO_0") (class "Default")
      (node (ref "U1") (pin "AD16") (pinfunction "P0.20_AD16") (pintype "bidirectional"))
      (node (ref "U7") (pin "5") (pinfunction "DI_5") (pintype "bidirectional"))
    )
    (net (code "42") (name "P0.21_QSPI_SCK") (class "Default")
      (node (ref "U1") (pin "AC17") (pinfunction "P0.21_AC17") (pintype "bidirectional"))
      (node (ref "U7") (pin "6") (pinfunction "CLK_6") (pintype "bidirectional"))
    )
    (net (code "43") (name "P0.22_QSPI_SIO_2") (class "Default")
      (node (ref "U1") (pin "AD18") (pinfunction "P0.22_AD18") (pintype "bidirectional"))
      (node (ref "U7") (pin "3") (pinfunction "~{WP}_3") (pintype "bidirectional"))
    )
    (net (code "44") (name "P0.23_QSPI_SIO_3") (class "Default")
      (node (ref "U1") (pin "AC19") (pinfunction "P0.23_AC19") (pintype "bidirectional"))
      (node (ref "U7") (pin "7") (pinfunction "~{HOLD}_7") (pintype "bidirectional"))
    )
    (net (code "45") (name "P0.24_QSPI_SIO_1") (class "Default")
      (node (ref "U1") (pin "AD20") (pinfunction "P0.24_AD20") (pintype "bidirectional"))
      (node (ref "U7") (pin "2") (pinfunction "DO_2") (pintype "bidirectional"))
    )
    (net (code "46") (name "P0.25_QSPI_CSN") (class "Default")
      (node (ref "U1") (pin "AC21") (pinfunction "P0.25_AC21") (pintype "bidirectional"))
      (node (ref "U7") (pin "1") (pinfunction "~{CS}_1") (pintype "bidirectional"))
    )
    (net (code "47") (name "P0.26_USER_RED") (class "Default")
      (node (ref "R7") (pin "2") (pinfunction "2_2") (pintype "passive"))
      (node (ref "U1") (pin "G1") (pinfunction "P0.26_G1") (pintype "bidirectional"))
    )
    (net (code "48") (name "P0.28_AIN4_LOW_A2_D2") (class "Default")
      (node (ref "J2") (pin "15") (pinfunction "3_15") (pintype "bidirectional"))
      (node (ref "J2") (pin "3") (pinfunction "3_3") (pintype "bidirectional"))
      (node (ref "U1") (pin "B11") (pinfunction "P0.28/AIN4_B11") (pintype "bidirectional"))
    )
    (net (code "49") (name "P0.29_AIN5_LOW_A3_D3") (class "Default")
      (node (ref "J2") (pin "16") (pinfunction "4_16") (pintype "bidirectional"))
      (node (ref "J2") (pin "4") (pinfunction "4_4") (pintype "bidirectional"))
      (node (ref "U1") (pin "A10") (pinfunction "P0.29/AIN5_A10") (pintype "bidirectional"))
    )
    (net (code "50") (name "P0.30_USER_GREEN") (class "Default")
      (node (ref "R4") (pin "2") (pinfunction "2_2") (pintype "passive"))
      (node (ref "U1") (pin "B9") (pinfunction "P0.30/AIN6_B9") (pintype "bidirectional"))
    )
    (net (code "51") (name "P0.31_AIN7_BAT") (class "Default")
      (node (ref "R16") (pin "2") (pinfunction "2_2") (pintype "passive"))
      (node (ref "R17") (pin "1") (pinfunction "1_1") (pintype "passive"))
      (node (ref "U1") (pin "A8") (pinfunction "P0.31/AIN7_A8") (pintype "bidirectional"))
    )
    (net (code "52") (name "P1.00_PDM_CLK") (class "Default")
      (node (ref "MIC1") (pin "2") (pinfunction "CLK_2") (pintype "bidirectional"))
      (node (ref "U1") (pin "AD22") (pinfunction "P1.00_AD22") (pintype "bidirectional"))
    )
    (net (code "53") (name "P1.10_MIC_PWR") (class "Default")
      (node (ref "C8") (pin "2") (pinfunction "2_2") (pintype "passive"))
      (node (ref "MIC1") (pin "1") (pinfunction "VDD_1") (pintype "bidirectional"))
      (node (ref "U1") (pin "A20") (pinfunction "P1.10_A20") (pintype "bidirectional"))
    )
    (net (code "54") (name "P1.11_TX_D6") (class "Default")
      (node (ref "J2") (pin "19") (pinfunction "7_19") (pintype "bidirectional"))
      (node (ref "J2") (pin "7") (pinfunction "7_7") (pintype "bidirectional"))
      (node (ref "U1") (pin "B19") (pinfunction "P1.11_B19") (pintype "bidirectional"))
    )
    (net (code "55") (name "P1.12_RX_D7") (class "Default")
      (node (ref "J1") (pin "1") (pinfunction "1_1") (pintype "bidirectional"))
      (node (ref "J1") (pin "13") (pinfunction "1_13") (pintype "bidirectional"))
      (node (ref "U1") (pin "B17") (pinfunction "P1.12_B17") (pintype "bidirectional"))
    )
    (net (code "56") (name "P1.13_SCK_D8") (class "Default")
      (node (ref "J1") (pin "14") (pinfunction "2_14") (pintype "bidirectional"))
      (node (ref "J1") (pin "2") (pinfunction "2_2") (pintype "bidirectional"))
      (node (ref "U1") (pin "A16") (pinfunction "P1.13_A16") (pintype "bidirectional"))
    )
    (net (code "57") (name "P1.14_MISO_D9") (class "Default")
      (node (ref "J1") (pin "15") (pinfunction "3_15") (pintype "bidirectional"))
      (node (ref "J1") (pin "3") (pinfunction "3_3") (pintype "bidirectional"))
      (node (ref "U1") (pin "B15") (pinfunction "P1.14_B15") (pintype "bidirectional"))
    )
    (net (code "58") (name "P1.15_MOSI_D10") (class "Default")
      (node (ref "J1") (pin "16") (pinfunction "4_16") (pintype "bidirectional"))
      (node (ref "J1") (pin "4") (pinfunction "4_4") (pintype "bidirectional"))
      (node (ref "U1") (pin "A14") (pinfunction "P1.15_A14") (pintype "bidirectional"))
    )
    (net (code "59") (name "PWR_LED") (class "Default")
      (node (ref "U1") (pin "R24") (pinfunction "P1.06_R24") (pintype "bidirectional"))
    )
    (net (code "60") (name "RESET") (class "Default")
      (node (ref "C5") (pin "1") (pinfunction "1_1") (pintype "passive"))
      (node (ref "K1") (pin "1") (pinfunction "A0_1") (pintype "bidirectional"))
      (node (ref "K1") (pin "3") (pinfunction "A1_3") (pintype "bidirectional"))
      (node (ref "R13") (pin "2") (pinfunction "2_2") (pintype "passive"))
      (node (ref "TP2") (pin "T") (pinfunction "T_T") (pintype "bidirectional"))
      (node (ref "U1") (pin "AC13") (pinfunction "P0.18/RESET_AC13") (pintype "bidirectional"))
    )
    (net (code "61") (name "SWDCLK") (class "Default")
      (node (ref "TP3") (pin "T") (pinfunction "T_T") (pintype "bidirectional"))
      (node (ref "U1") (pin "AA24") (pinfunction "SWDCLK_AA24") (pintype "input"))
    )
    (net (code "62") (name "SWDIO") (class "Default")
      (node (ref "TP5") (pin "T") (pinfunction "T_T") (pintype "bidirectional"))
      (node (ref "U1") (pin "AC24") (pinfunction "SWDIO_AC24") (pintype "bidirectional"))
    )
    (net (code "63") (name "USB_D+") (class "Default")
      (node (ref "R11") (pin "1") (pinfunction "1_1") (pintype "passive"))
      (node (ref "USB1") (pin "A6") (pinfunction "A6/DP1_A6") (pintype "bidirectional"))
      (node (ref "USB1") (pin "B6") (pinfunction "B6/DP2_B6") (pintype "bidirectional"))
    )
    (net (code "64") (name "USB_D-") (class "Default")
      (node (ref "R10") (pin "1") (pinfunction "1_1") (pintype "passive"))
      (node (ref "USB1") (pin "A7") (pinfunction "A7/DN1_A7") (pintype "bidirectional"))
      (node (ref "USB1") (pin "B7") (pinfunction "B7/DN2_B7") (pintype "bidirectional"))
    )
    (net (code "65") (name "VBAT") (class "Default")
      (node (ref "BAT") (pin "1") (pinfunction "T_1") (pintype "bidirectional"))
      (node (ref "C30") (pin "1") (pinfunction "1_1") (pintype "passive"))
      (node (ref "Q1") (pin "1") (pinfunction "D_1") (pintype "bidirectional"))
      (node (ref "R16") (pin "1") (pinfunction "1_1") (pintype "passive"))
      (node (ref "U2") (pin "A1") (pinfunction "OUT_A1") (pintype "bidirectional"))
    )
    (net (code "66") (name "VBUS") (class "Default")
      (node (ref "C25") (pin "2") (pinfunction "2_2") (pintype "passive"))
      (node (ref "C9") (pin "2") (pinfunction "2_2") (pintype "passive"))
      (node (ref "D1") (pin "+") (pinfunction "+_+") (pintype "passive"))
      (node (ref "J1") (pin "19") (pinfunction "7_19") (pintype "bidirectional"))
      (node (ref "J1") (pin "7") (pinfunction "7_7") (pintype "bidirectional"))
      (node (ref "Q1") (pin "2") (pinfunction "G_2") (pintype "bidirectional"))
      (node (ref "R9") (pin "2") (pinfunction "2_2") (pintype "passive"))
      (node (ref "U1") (pin "AD2") (pinfunction "VBUS_AD2") (pintype "bidirectional"))
      (node (ref "U2") (pin "A2") (pinfunction "IN_A2") (pintype "bidirectional"))
      (node (ref "USB1") (pin "A4_B9") (pinfunction "A4/B9/VBUS_A4_B9") (pintype "bidirectional"))
      (node (ref "USB1") (pin "B4_A9") (pinfunction "B4/A9/VBUS_B4_A9") (pintype "bidirectional"))
    )
    (net (code "67") (name "VIN") (class "Default")
      (node (ref "C4") (pin "1") (pinfunction "1_1") (pintype "passive"))
      (node (ref "D1") (pin "-") (pinfunction "-_-") (pintype "passive"))
      (node (ref "Q1") (pin "3") (pinfunction "S_3") (pintype "bidirectional"))
      (node (ref "U6") (pin "3") (pinfunction "EN_3") (pintype "bidirectional"))
      (node (ref "U6") (pin "4") (pinfunction "IN_4") (pintype "bidirectional"))
    )
    (net (code "68") (name "unconnected-(U1-DCCH-PadAB2)") (class "Default")
      (node (ref "U1") (pin "AB2") (pinfunction "DCCH_AB2") (pintype "bidirectional"))
    )
    (net (code "69") (name "unconnected-(U1-P0.08-PadN1)") (class "Default")
      (node (ref "U1") (pin "N1") (pinfunction "P0.08_N1") (pintype "bidirectional"))
    )
    (net (code "70") (name "unconnected-(U1-P0.12-PadU1)") (class "Default")
      (node (ref "U1") (pin "U1") (pinfunction "P0.12_U1") (pintype "bidirectional"))
    )
    (net (code "71") (name "unconnected-(U1-P0.15-PadAD10)") (class "Default")
      (node (ref "U1") (pin "AD10") (pinfunction "P0.15_AD10") (pintype "bidirectional"))
    )
    (net (code "72") (name "unconnected-(U1-P0.19-PadAC15)") (class "Default")
      (node (ref "U1") (pin "AC15") (pinfunction "P0.19_AC15") (pintype "bidirectional"))
    )
    (net (code "73") (name "unconnected-(U1-P1.01-PadY23)") (class "Default")
      (node (ref "U1") (pin "Y23") (pinfunction "P1.01_Y23") (pintype "bidirectional"))
    )
    (net (code "74") (name "unconnected-(U1-P1.02-PadW24)") (class "Default")
      (node (ref "U1") (pin "W24") (pinfunction "P1.02_W24") (pintype "bidirectional"))
    )
    (net (code "75") (name "unconnected-(U1-P1.03-PadV23)") (class "Default")
      (node (ref "U1") (pin "V23") (pinfunction "P1.03_V23") (pintype "bidirectional"))
    )
    (net (code "76") (name "unconnected-(U1-P1.04-PadU24)") (class "Default")
      (node (ref "U1") (pin "U24") (pinfunction "P1.04_U24") (pintype "bidirectional"))
    )
    (net (code "77") (name "unconnected-(U1-P1.05-PadT23)") (class "Default")
      (node (ref "U1") (pin "T23") (pinfunction "P1.05_T23") (pintype "bidirectional"))
    )
    (net (code "78") (name "unconnected-(U1-P1.07-PadP23)") (class "Default")
      (node (ref "U1") (pin "P23") (pinfunction "P1.07_P23") (pintype "bidirectional"))
    )
    (net (code "79") (name "unconnected-(U1-P1.09-PadR1)") (class "Default")
      (node (ref "U1") (pin "R1") (pinfunction "P1.09_R1") (pintype "bidirectional"))
    )
    (net (code "80") (name "unconnected-(U3-INT2-Pad9)") (class "Default")
      (node (ref "U3") (pin "9") (pinfunction "INT2_9") (pintype "bidirectional"))
    )
    (net (code "81") (name "unconnected-(U3-NC-Pad10)") (class "Default")
      (node (ref "U3") (pin "10") (pinfunction "NC_10") (pintype "bidirectional"))
    )
    (net (code "82") (name "unconnected-(U3-NC-Pad11)") (class "Default")
      (node (ref "U3") (pin "11") (pinfunction "NC_11") (pintype "bidirectional"))
    )
    (net (code "83") (name "unconnected-(USB1-A8{slash}SBU1-PadA8)") (class "Default")
      (node (ref "USB1") (pin "A8") (pinfunction "A8/SBU1_A8") (pintype "bidirectional"))
    )
    (net (code "84") (name "unconnected-(USB1-B8{slash}SBU2-PadB8)") (class "Default")
      (node (ref "USB1") (pin "B8") (pinfunction "B8/SBU2_B8") (pintype "bidirectional"))
    )
    (net (code "85") (name "{slash}CE") (class "Default")
      (node (ref "R20") (pin "1") (pinfunction "1_1") (pintype "passive"))
      (node (ref "U2") (pin "B1") (pinfunction "TS_B1") (pintype "bidirectional"))
    )
  )
)
